# EPS_Local-Supply_Channel.net
KiCad netlist of a schematic drawn in Altium Designer
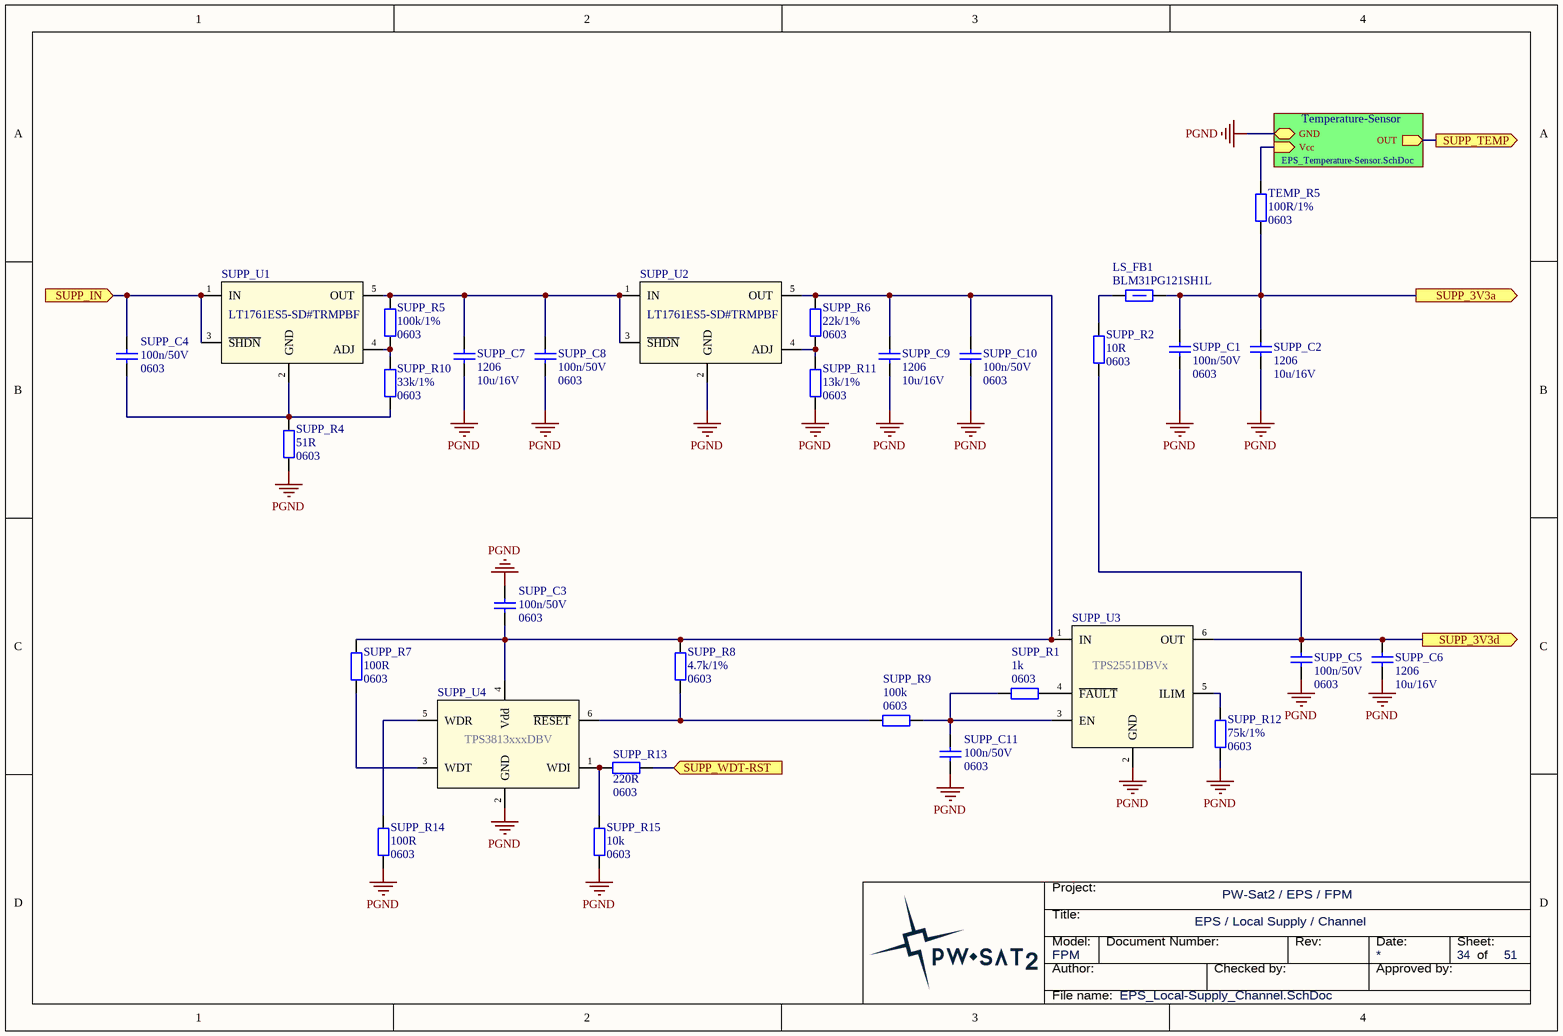
[diagram p0: EPS_Local-Supply_Channel.SchDoc]

(export (version "E")
  (design (tool "Eeschema 10.0.6"))
  (components
    (comp (ref "LS_FB1")
      (value "120R/100MHz")
      (footprint "SMD_FerriteBead_1206")
      (description "Ferrite bead, 1206, 0.02HM, 3.5A.")
      (fields (field (name "MANUFACTURER") "Murata") (field (name "MANUFACTURERPARTNUMBER") "BLM31PG121SH1L"))
      (libsource (lib "inductors") (part "BLM31PG121SH1L"))
    )
    (comp (ref "SUPP_C1")
      (value "100n/50V")
      (footprint "SMD_Capacitor_0603")
      (description "Ceramic Cap Kemet COTS 100n/50V X7R 0603")
      (fields
        (field (name "MANUFACTURER") "Kemet")
        (field (name "MANUFACTURERPARTNUMBER") "C0603T104K5RALTU")
        (field (name "PACKAGE") "0603")
      )
      (libsource (lib "capacitors") (part "Cer_C0603T104K5RALTU"))
    )
    (comp (ref "SUPP_C2")
      (value "10u/16V")
      (footprint "SMD_Capacitor_1206")
      (description "Ceramic Cap Kemet COTS 10u/16V X7R 1206")
      (fields
        (field (name "MANUFACTURERPARTNUMBER") "C1206T106K4RACTU")
        (field (name "MANUFACTURER") "Kemet")
        (field (name "PACKGE") "1206")
      )
      (libsource (lib "capacitors") (part "Cer_C1206T106K4RACTU"))
    )
    (comp (ref "SUPP_C3")
      (value "100n/50V")
      (footprint "SMD_Capacitor_0603")
      (description "Ceramic Cap Kemet COTS 100n/50V X7R 0603")
      (fields
        (field (name "MANUFACTURER") "Kemet")
        (field (name "MANUFACTURERPARTNUMBER") "C0603T104K5RALTU")
        (field (name "PACKAGE") "0603")
      )
      (libsource (lib "capacitors") (part "Cer_C0603T104K5RALTU"))
    )
    (comp (ref "SUPP_C4")
      (value "100n/50V")
      (footprint "SMD_Capacitor_0603")
      (description "Ceramic Cap Kemet COTS 100n/50V X7R 0603")
      (fields
        (field (name "MANUFACTURER") "Kemet")
        (field (name "MANUFACTURERPARTNUMBER") "C0603T104K5RALTU")
        (field (name "PACKAGE") "0603")
      )
      (libsource (lib "capacitors") (part "Cer_C0603T104K5RALTU"))
    )
    (comp (ref "SUPP_C5")
      (value "100n/50V")
      (footprint "SMD_Capacitor_0603")
      (description "Ceramic Cap Kemet COTS 100n/50V X7R 0603")
      (fields
        (field (name "MANUFACTURER") "Kemet")
        (field (name "MANUFACTURERPARTNUMBER") "C0603T104K5RALTU")
        (field (name "PACKAGE") "0603")
      )
      (libsource (lib "capacitors") (part "Cer_C0603T104K5RALTU"))
    )
    (comp (ref "SUPP_C6")
      (value "10u/16V")
      (footprint "SMD_Capacitor_1206")
      (description "Ceramic Cap Kemet COTS 10u/16V X7R 1206")
      (fields
        (field (name "MANUFACTURERPARTNUMBER") "C1206T106K4RACTU")
        (field (name "MANUFACTURER") "Kemet")
        (field (name "PACKGE") "1206")
      )
      (libsource (lib "capacitors") (part "Cer_C1206T106K4RACTU"))
    )
    (comp (ref "SUPP_C7")
      (value "10u/16V")
      (footprint "SMD_Capacitor_1206")
      (description "Ceramic Cap Kemet COTS 10u/16V X7R 1206")
      (fields
        (field (name "MANUFACTURERPARTNUMBER") "C1206T106K4RACTU")
        (field (name "MANUFACTURER") "Kemet")
        (field (name "PACKGE") "1206")
      )
      (libsource (lib "capacitors") (part "Cer_C1206T106K4RACTU"))
    )
    (comp (ref "SUPP_C8")
      (value "100n/50V")
      (footprint "SMD_Capacitor_0603")
      (description "Ceramic Cap Kemet COTS 100n/50V X7R 0603")
      (fields
        (field (name "MANUFACTURER") "Kemet")
        (field (name "MANUFACTURERPARTNUMBER") "C0603T104K5RALTU")
        (field (name "PACKAGE") "0603")
      )
      (libsource (lib "capacitors") (part "Cer_C0603T104K5RALTU"))
    )
    (comp (ref "SUPP_C9")
      (value "10u/16V")
      (footprint "SMD_Capacitor_1206")
      (description "Ceramic Cap Kemet COTS 10u/16V X7R 1206")
      (fields
        (field (name "MANUFACTURERPARTNUMBER") "C1206T106K4RACTU")
        (field (name "MANUFACTURER") "Kemet")
        (field (name "PACKGE") "1206")
      )
      (libsource (lib "capacitors") (part "Cer_C1206T106K4RACTU"))
    )
    (comp (ref "SUPP_C10")
      (value "100n/50V")
      (footprint "SMD_Capacitor_0603")
      (description "Ceramic Cap Kemet COTS 100n/50V X7R 0603")
      (fields
        (field (name "MANUFACTURER") "Kemet")
        (field (name "MANUFACTURERPARTNUMBER") "C0603T104K5RALTU")
        (field (name "PACKAGE") "0603")
      )
      (libsource (lib "capacitors") (part "Cer_C0603T104K5RALTU"))
    )
    (comp (ref "SUPP_C11")
      (value "100n/50V")
      (footprint "SMD_Capacitor_0603")
      (description "Ceramic Cap Kemet COTS 100n/50V X7R 0603")
      (fields
        (field (name "MANUFACTURER") "Kemet")
        (field (name "MANUFACTURERPARTNUMBER") "C0603T104K5RALTU")
        (field (name "PACKAGE") "0603")
      )
      (libsource (lib "capacitors") (part "Cer_C0603T104K5RALTU"))
    )
    (comp (ref "SUPP_R1")
      (value "1k")
      (footprint "SMD_Resistor_0603")
      (fields (field (name "PACKAGE") "0603"))
      (libsource (lib "resistors") (part "Res"))
    )
    (comp (ref "SUPP_R2")
      (value "10R")
      (footprint "SMD_Resistor_0603")
      (fields (field (name "PACKAGE") "0603"))
      (libsource (lib "") (part "Res_3"))
    )
    (comp (ref "SUPP_R4")
      (value "51R")
      (footprint "SMD_Resistor_0603")
      (fields (field (name "PACKAGE") "0603"))
      (libsource (lib "") (part "Res_1"))
    )
    (comp (ref "SUPP_R5")
      (value "100k/1%")
      (footprint "SMD_Resistor_0603")
      (fields (field (name "PACKAGE") "0603"))
      (libsource (lib "") (part "Res_1"))
    )
    (comp (ref "SUPP_R6")
      (value "22k/1%")
      (footprint "SMD_Resistor_0603")
      (fields (field (name "PACKAGE") "0603"))
      (libsource (lib "") (part "Res_1"))
    )
    (comp (ref "SUPP_R7")
      (value "100R")
      (footprint "SMD_Resistor_0603")
      (fields (field (name "PACKAGE") "0603"))
      (libsource (lib "") (part "Res_1"))
    )
    (comp (ref "SUPP_R8")
      (value "4.7k/1%")
      (footprint "SMD_Resistor_0603")
      (fields (field (name "PACKAGE") "0603"))
      (libsource (lib "") (part "Res_1"))
    )
    (comp (ref "SUPP_R9")
      (value "100k")
      (footprint "SMD_Resistor_0603")
      (fields (field (name "PACKAGE") "0603"))
      (libsource (lib "resistors") (part "Res"))
    )
    (comp (ref "SUPP_R10")
      (value "33k/1%")
      (footprint "SMD_Resistor_0603")
      (fields (field (name "PACKAGE") "0603"))
      (libsource (lib "") (part "Res_1"))
    )
    (comp (ref "SUPP_R11")
      (value "13k/1%")
      (footprint "SMD_Resistor_0603")
      (fields (field (name "PACKAGE") "0603"))
      (libsource (lib "") (part "Res_1"))
    )
    (comp (ref "SUPP_R12")
      (value "75k/1%")
      (footprint "SMD_Resistor_0603")
      (fields (field (name "PACKAGE") "0603"))
      (libsource (lib "") (part "Res_1"))
    )
    (comp (ref "SUPP_R13")
      (value "220R")
      (footprint "SMD_Resistor_0603")
      (fields (field (name "PACKAGE") "0603"))
      (libsource (lib "") (part "Res_2"))
    )
    (comp (ref "SUPP_R14")
      (value "100R")
      (footprint "SMD_Resistor_0603")
      (fields (field (name "PACKAGE") "0603"))
      (libsource (lib "") (part "Res_1"))
    )
    (comp (ref "SUPP_R15")
      (value "10k")
      (footprint "SMD_Resistor_0603")
      (fields (field (name "PACKAGE") "0603"))
      (libsource (lib "") (part "Res_3"))
    )
    (comp (ref "SUPP_U1")
      (value "LT1761ES5-SD#TRMPBF")
      (footprint "SOT23-5")
      (description "100mA, Regulated, Low Noise, LDO Micropower Regulator in TSOT-23")
      (fields (field (name "MANUFACTURER") "Linear Technology"))
      (libsource (lib "microcircuits") (part "LT1761ES5-SD#TRMPBF"))
    )
    (comp (ref "SUPP_U2")
      (value "LT1761ES5-SD#TRMPBF")
      (footprint "SOT23-5")
      (description "100mA, Regulated, Low Noise, LDO Micropower Regulator in TSOT-23")
      (fields (field (name "MANUFACTURER") "Linear Technology"))
      (libsource (lib "microcircuits") (part "LT1761ES5-SD#TRMPBF"))
    )
    (comp (ref "SUPP_U3")
      (value "TPS2551DBVx")
      (footprint "SOT23-6")
      (description "Adjustable Current-Limited Power-Distribution Switch.")
      (fields (field (name "MANUFACTURER") "Texas Instruments"))
      (libsource (lib "microcircuits") (part "TPS2551DBVx"))
    )
    (comp (ref "SUPP_U4")
      (value "TPS3813xxxDBV")
      (footprint "SOT23-6")
      (description "Processor Supervisory Circuits with Window-Watchdog.")
      (fields (field (name "MANUFACTURER") "Texas Instruments"))
      (libsource (lib "microcircuits") (part "TPS3813xxxDBV"))
    )
    (comp (ref "TEMP_R5")
      (value "100R/1%")
      (footprint "SMD_Resistor_0603")
      (description "1k/1% Vishay CRCW 0603 Resistor. 100mW, 100ppm, 75V.")
      (fields
        (field (name "MANUFACTURER") "Vishay")
        (field (name "MANUFACTURERPARTNUMBER") "CRCW06031K00FKxxxx")
        (field (name "PACKAGE") "0603")
      )
      (libsource (lib "resistors") (part "CRCW06031K00FKxxxx"))
    )
  )
  (nets
    (net (code "1") (name "/SUPP_3V3a") (class "Default")
      (node (ref "LS_FB1") (pin "2") (pinfunction "2_2") (pintype "passive"))
      (node (ref "SUPP_C1") (pin "1") (pinfunction "1_1") (pintype "passive"))
      (node (ref "SUPP_C2") (pin "1") (pinfunction "1_1") (pintype "passive"))
      (node (ref "TEMP_R5") (pin "2") (pinfunction "2_2") (pintype "passive"))
    )
    (net (code "2") (name "/SUPP_3V3d") (class "Default")
      (node (ref "SUPP_C5") (pin "1") (pinfunction "1_1") (pintype "passive"))
      (node (ref "SUPP_C6") (pin "1") (pinfunction "1_1") (pintype "passive"))
      (node (ref "SUPP_R2") (pin "1") (pinfunction "1_1") (pintype "passive"))
      (node (ref "SUPP_U3") (pin "6") (pinfunction "OUT_6") (pintype "passive"))
    )
    (net (code "3") (name "/SUPP_IN") (class "Default")
      (node (ref "SUPP_C4") (pin "1") (pinfunction "1_1") (pintype "passive"))
      (node (ref "SUPP_U1") (pin "1") (pinfunction "IN_1") (pintype "passive"))
      (node (ref "SUPP_U1") (pin "3") (pinfunction "~{SHDN}_3") (pintype "passive"))
    )
    (net (code "5") (name "/SUPP_WDT-RST") (class "Default")
      (node (ref "SUPP_R13") (pin "2") (pinfunction "2_2") (pintype "passive"))
    )
    (net (code "6") (name "/Vcc") (class "Default")
      (node (ref "TEMP_R5") (pin "1") (pinfunction "1_1") (pintype "passive"))
    )
    (net (code "7") (name "Net-(LS_FB1-Pad1)") (class "Default")
      (node (ref "LS_FB1") (pin "1") (pinfunction "1_1") (pintype "passive"))
      (node (ref "SUPP_R2") (pin "2") (pinfunction "2_2") (pintype "passive"))
    )
    (net (code "8") (name "Net-(SUPP_U1-ADJ)") (class "Default")
      (node (ref "SUPP_R10") (pin "1") (pinfunction "1_1") (pintype "passive"))
      (node (ref "SUPP_R5") (pin "2") (pinfunction "2_2") (pintype "passive"))
      (node (ref "SUPP_U1") (pin "4") (pinfunction "ADJ_4") (pintype "passive"))
    )
    (net (code "9") (name "Net-(SUPP_U1-GND)") (class "Default")
      (node (ref "SUPP_C4") (pin "2") (pinfunction "2_2") (pintype "passive"))
      (node (ref "SUPP_R10") (pin "2") (pinfunction "2_2") (pintype "passive"))
      (node (ref "SUPP_R4") (pin "1") (pinfunction "1_1") (pintype "passive"))
      (node (ref "SUPP_U1") (pin "2") (pinfunction "GND_2") (pintype "passive"))
    )
    (net (code "10") (name "Net-(SUPP_U1-OUT)") (class "Default")
      (node (ref "SUPP_C7") (pin "1") (pinfunction "1_1") (pintype "passive"))
      (node (ref "SUPP_C8") (pin "1") (pinfunction "1_1") (pintype "passive"))
      (node (ref "SUPP_R5") (pin "1") (pinfunction "1_1") (pintype "passive"))
      (node (ref "SUPP_U1") (pin "5") (pinfunction "OUT_5") (pintype "passive"))
      (node (ref "SUPP_U2") (pin "1") (pinfunction "IN_1") (pintype "passive"))
      (node (ref "SUPP_U2") (pin "3") (pinfunction "~{SHDN}_3") (pintype "passive"))
    )
    (net (code "11") (name "Net-(SUPP_U2-ADJ)") (class "Default")
      (node (ref "SUPP_R11") (pin "1") (pinfunction "1_1") (pintype "passive"))
      (node (ref "SUPP_R6") (pin "2") (pinfunction "2_2") (pintype "passive"))
      (node (ref "SUPP_U2") (pin "4") (pinfunction "ADJ_4") (pintype "passive"))
    )
    (net (code "12") (name "Net-(SUPP_U2-OUT)") (class "Default")
      (node (ref "SUPP_C10") (pin "1") (pinfunction "1_1") (pintype "passive"))
      (node (ref "SUPP_C3") (pin "2") (pinfunction "2_2") (pintype "passive"))
      (node (ref "SUPP_C9") (pin "1") (pinfunction "1_1") (pintype "passive"))
      (node (ref "SUPP_R6") (pin "1") (pinfunction "1_1") (pintype "passive"))
      (node (ref "SUPP_R7") (pin "1") (pinfunction "1_1") (pintype "passive"))
      (node (ref "SUPP_R8") (pin "1") (pinfunction "1_1") (pintype "passive"))
      (node (ref "SUPP_U2") (pin "5") (pinfunction "OUT_5") (pintype "passive"))
      (node (ref "SUPP_U3") (pin "1") (pinfunction "IN_1") (pintype "passive"))
      (node (ref "SUPP_U4") (pin "4") (pinfunction "Vdd_4") (pintype "passive"))
    )
    (net (code "13") (name "Net-(SUPP_U3-EN)") (class "Default")
      (node (ref "SUPP_C11") (pin "2") (pinfunction "2_2") (pintype "passive"))
      (node (ref "SUPP_R1") (pin "2") (pinfunction "2_2") (pintype "passive"))
      (node (ref "SUPP_R9") (pin "1") (pinfunction "1_1") (pintype "passive"))
      (node (ref "SUPP_U3") (pin "3") (pinfunction "EN_3") (pintype "passive"))
    )
    (net (code "14") (name "Net-(SUPP_U3-ILIM)") (class "Default")
      (node (ref "SUPP_R12") (pin "1") (pinfunction "1_1") (pintype "passive"))
      (node (ref "SUPP_U3") (pin "5") (pinfunction "ILIM_5") (pintype "passive"))
    )
    (net (code "15") (name "Net-(SUPP_U3-~{FAULT})") (class "Default")
      (node (ref "SUPP_R1") (pin "1") (pinfunction "1_1") (pintype "passive"))
      (node (ref "SUPP_U3") (pin "4") (pinfunction "~{FAULT}_4") (pintype "passive"))
    )
    (net (code "16") (name "Net-(SUPP_U4-WDI)") (class "Default")
      (node (ref "SUPP_R13") (pin "1") (pinfunction "1_1") (pintype "passive"))
      (node (ref "SUPP_R15") (pin "2") (pinfunction "2_2") (pintype "passive"))
      (node (ref "SUPP_U4") (pin "1") (pinfunction "WDI_1") (pintype "passive"))
    )
    (net (code "17") (name "Net-(SUPP_U4-WDR)") (class "Default")
      (node (ref "SUPP_R14") (pin "1") (pinfunction "1_1") (pintype "passive"))
      (node (ref "SUPP_U4") (pin "5") (pinfunction "WDR_5") (pintype "passive"))
    )
    (net (code "18") (name "Net-(SUPP_U4-WDT)") (class "Default")
      (node (ref "SUPP_R7") (pin "2") (pinfunction "2_2") (pintype "passive"))
      (node (ref "SUPP_U4") (pin "3") (pinfunction "WDT_3") (pintype "passive"))
    )
    (net (code "19") (name "Net-(SUPP_U4-~{RESET})") (class "Default")
      (node (ref "SUPP_R8") (pin "2") (pinfunction "2_2") (pintype "passive"))
      (node (ref "SUPP_R9") (pin "2") (pinfunction "2_2") (pintype "passive"))
      (node (ref "SUPP_U4") (pin "6") (pinfunction "~{RESET}_6") (pintype "passive"))
    )
    (net (code "20") (name "PGND") (class "Default")
      (node (ref "SUPP_C1") (pin "2") (pinfunction "2_2") (pintype "passive"))
      (node (ref "SUPP_C10") (pin "2") (pinfunction "2_2") (pintype "passive"))
      (node (ref "SUPP_C11") (pin "1") (pinfunction "1_1") (pintype "passive"))
      (node (ref "SUPP_C2") (pin "2") (pinfunction "2_2") (pintype "passive"))
      (node (ref "SUPP_C3") (pin "1") (pinfunction "1_1") (pintype "passive"))
      (node (ref "SUPP_C5") (pin "2") (pinfunction "2_2") (pintype "passive"))
      (node (ref "SUPP_C6") (pin "2") (pinfunction "2_2") (pintype "passive"))
      (node (ref "SUPP_C7") (pin "2") (pinfunction "2_2") (pintype "passive"))
      (node (ref "SUPP_C8") (pin "2") (pinfunction "2_2") (pintype "passive"))
      (node (ref "SUPP_C9") (pin "2") (pinfunction "2_2") (pintype "passive"))
      (node (ref "SUPP_R11") (pin "2") (pinfunction "2_2") (pintype "passive"))
      (node (ref "SUPP_R12") (pin "2") (pinfunction "2_2") (pintype "passive"))
      (node (ref "SUPP_R14") (pin "2") (pinfunction "2_2") (pintype "passive"))
      (node (ref "SUPP_R15") (pin "1") (pinfunction "1_1") (pintype "passive"))
      (node (ref "SUPP_R4") (pin "2") (pinfunction "2_2") (pintype "passive"))
      (node (ref "SUPP_U2") (pin "2") (pinfunction "GND_2") (pintype "passive"))
      (node (ref "SUPP_U3") (pin "2") (pinfunction "GND_2") (pintype "passive"))
      (node (ref "SUPP_U4") (pin "2") (pinfunction "GND_2") (pintype "passive"))
    )
  )
)
